# CANBed2040.net
KiCad netlist of a schematic drawn in EAGLE
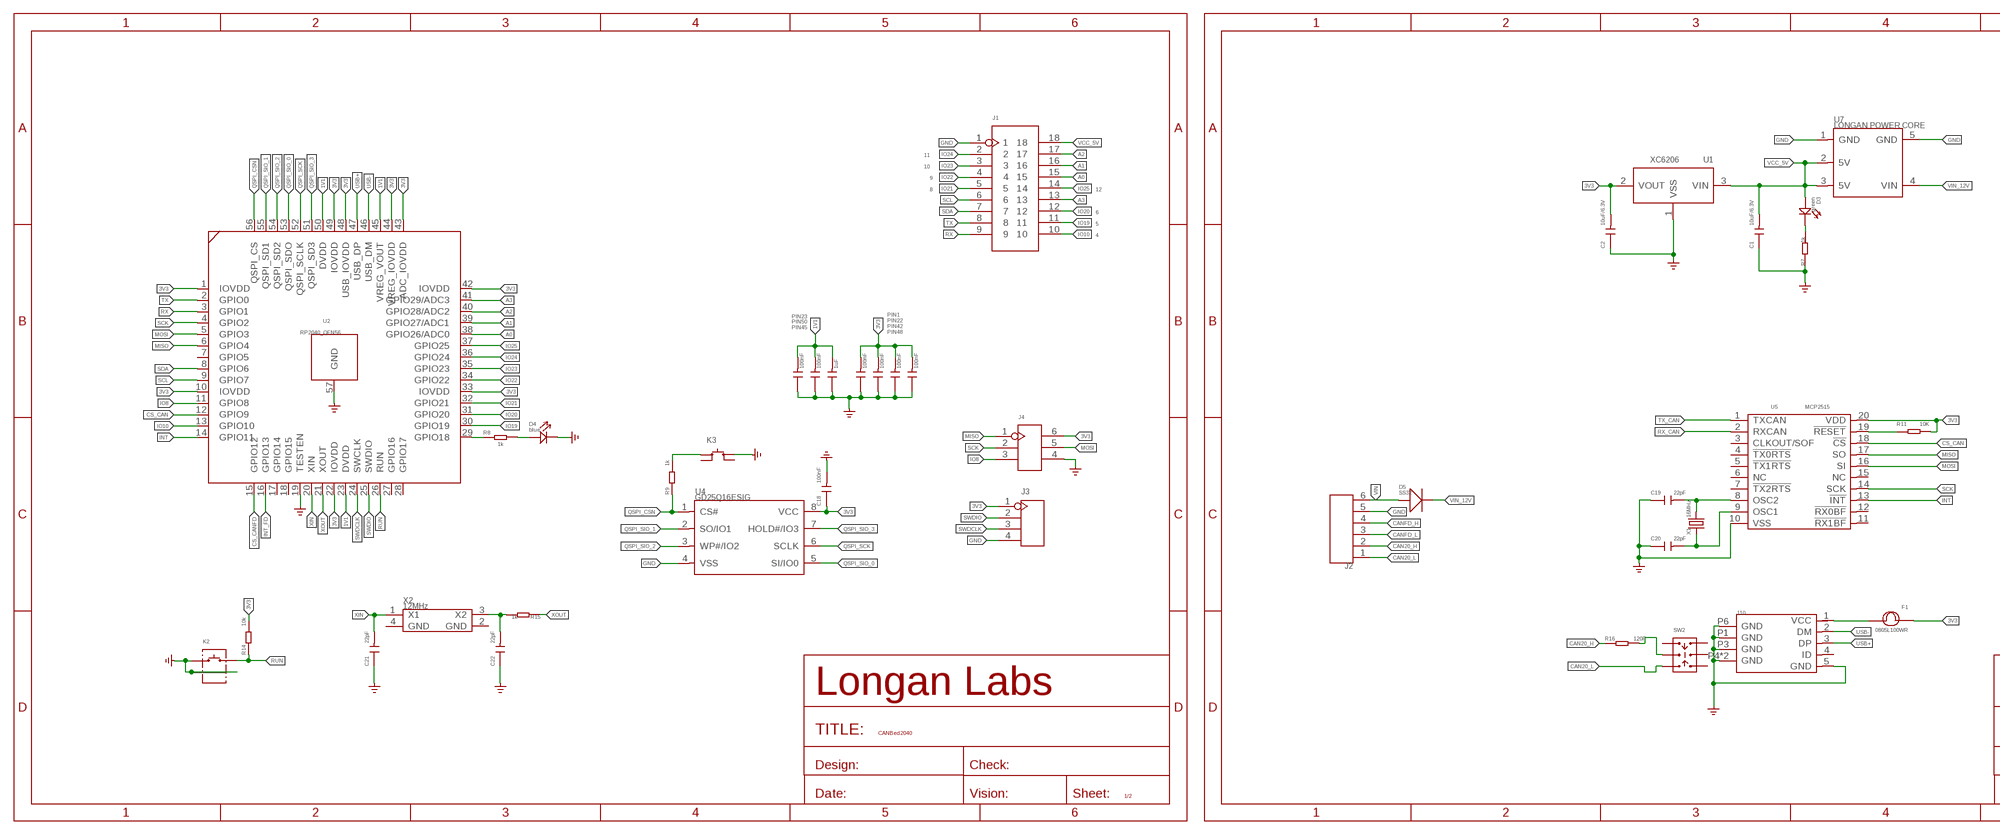
[diagram p0: schematic, sheet 1, part 1 of 2]
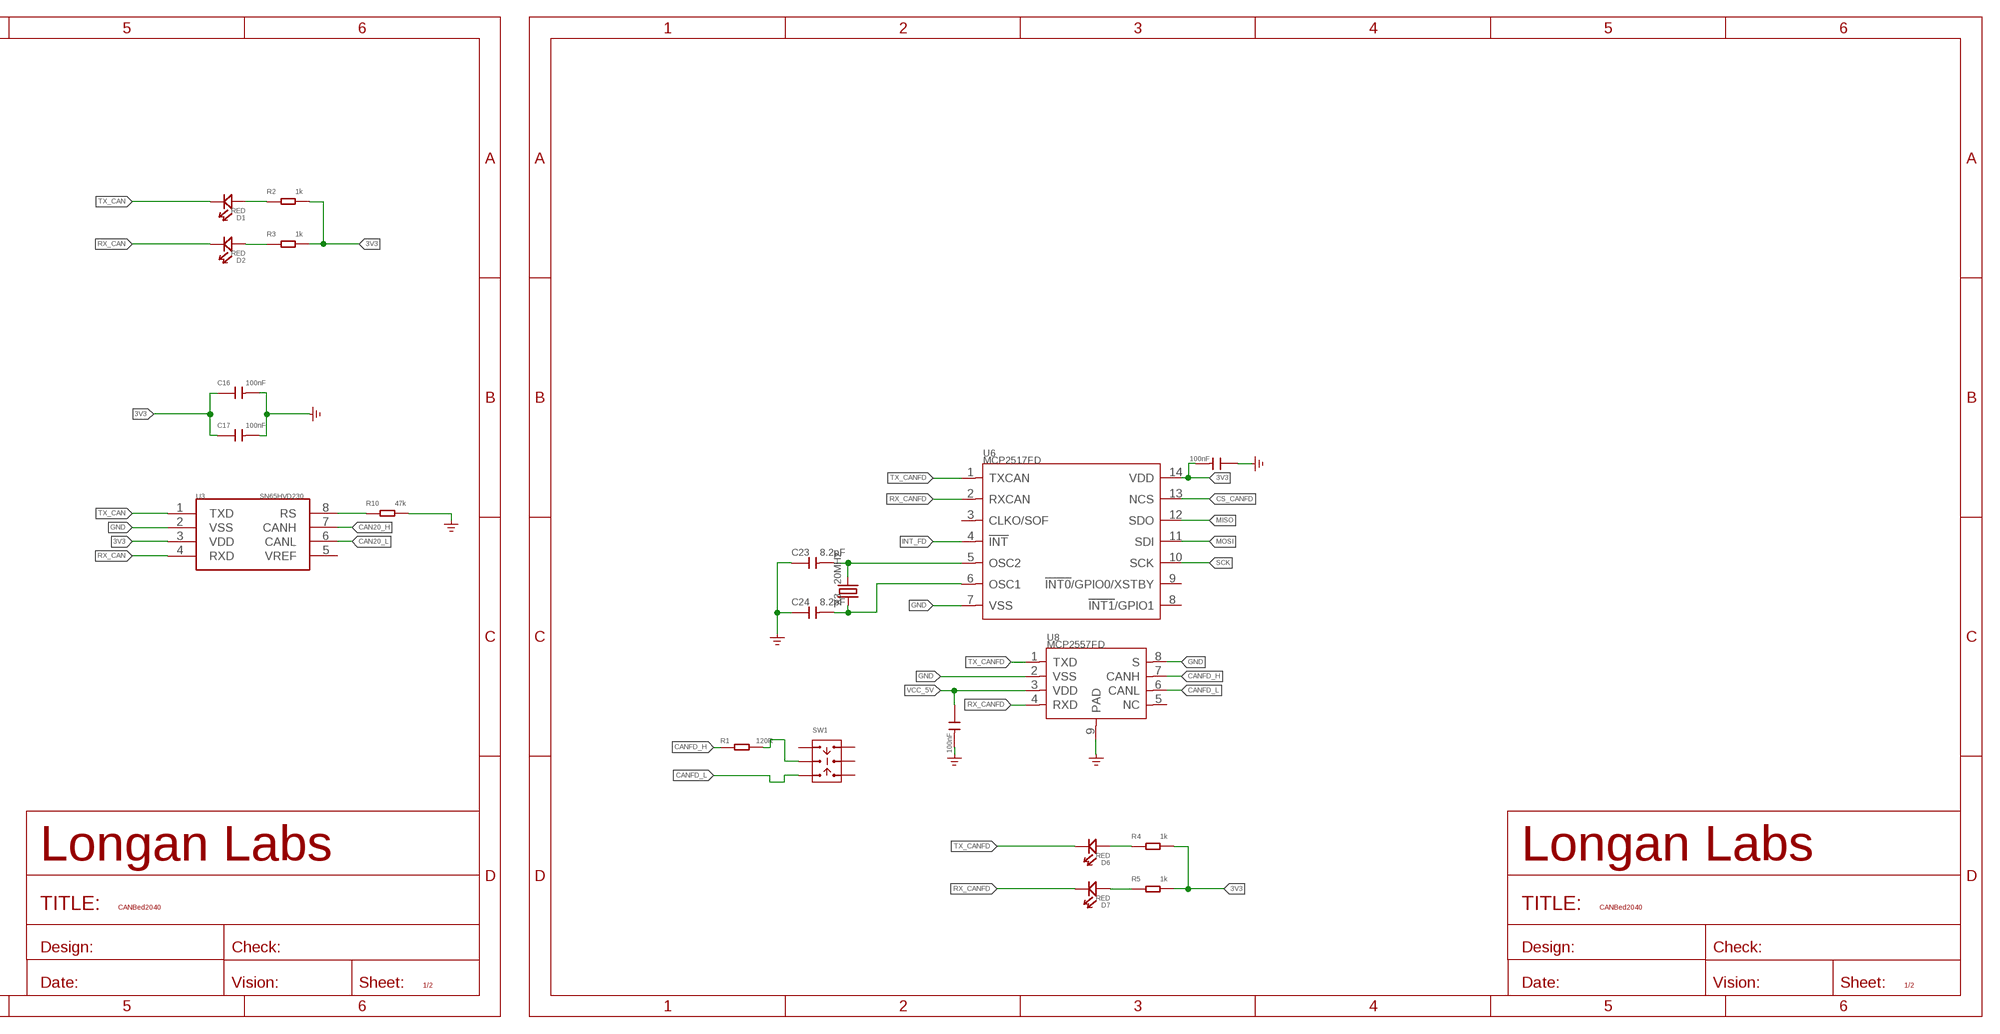
[diagram p1: schematic, sheet 1, part 2 of 2]

(export (version "E")
  (design (tool "Eeschema 10.0.6"))
  (components
    (comp (ref "C1")
      (value "10uF/6.3V")
      (footprint "eagle-import:C0603")
      (libsource (lib "eagle-import") (part "CAP-0603"))
    )
    (comp (ref "C2")
      (value "10uF/6.3V")
      (footprint "eagle-import:C0603")
      (libsource (lib "eagle-import") (part "CAP-0603"))
    )
    (comp (ref "C9")
      (value "100nF")
      (footprint "eagle-import:C0603")
      (libsource (lib "eagle-import") (part "CAP-0603"))
    )
    (comp (ref "C10")
      (value "100nF")
      (footprint "eagle-import:C0603")
      (libsource (lib "eagle-import") (part "CAP-0603"))
    )
    (comp (ref "C11")
      (value "1uF")
      (footprint "eagle-import:C0603")
      (libsource (lib "eagle-import") (part "CAP-0603"))
    )
    (comp (ref "C12")
      (value "100nF")
      (footprint "eagle-import:C0603")
      (libsource (lib "eagle-import") (part "CAP-0603"))
    )
    (comp (ref "C13")
      (value "100nF")
      (footprint "eagle-import:C0603")
      (libsource (lib "eagle-import") (part "CAP-0603"))
    )
    (comp (ref "C14")
      (value "100nF")
      (footprint "eagle-import:C0603")
      (libsource (lib "eagle-import") (part "CAP-0603"))
    )
    (comp (ref "C15")
      (value "100nF")
      (footprint "eagle-import:C0603")
      (libsource (lib "eagle-import") (part "CAP-0603"))
    )
    (comp (ref "C16")
      (value "100nF")
      (footprint "eagle-import:C0603")
      (libsource (lib "eagle-import") (part "CAP-0603"))
    )
    (comp (ref "C17")
      (value "100nF")
      (footprint "eagle-import:C0603")
      (libsource (lib "eagle-import") (part "CAP-0603"))
    )
    (comp (ref "C18")
      (value "100nF")
      (footprint "eagle-import:C0603")
      (libsource (lib "eagle-import") (part "CAP-0603"))
    )
    (comp (ref "C19")
      (value "22pF")
      (footprint "eagle-import:C0603")
      (libsource (lib "eagle-import") (part "CAP-0603"))
    )
    (comp (ref "C20")
      (value "22pF")
      (footprint "eagle-import:C0603")
      (libsource (lib "eagle-import") (part "CAP-0603"))
    )
    (comp (ref "C21")
      (value "22pF")
      (footprint "eagle-import:C0603")
      (libsource (lib "eagle-import") (part "CAP-0603"))
    )
    (comp (ref "C22")
      (value "22pF")
      (footprint "eagle-import:C0603")
      (libsource (lib "eagle-import") (part "CAP-0603"))
    )
    (comp (ref "C23")
      (value "8.2pF")
      (footprint "eagle-import:C0603")
      (libsource (lib "eagle-import") (part "CAP-0603"))
    )
    (comp (ref "C24")
      (value "8.2pF")
      (footprint "eagle-import:C0603")
      (libsource (lib "eagle-import") (part "CAP-0603"))
    )
    (comp (ref "C25")
      (value "100nF")
      (footprint "eagle-import:C0603")
      (libsource (lib "eagle-import") (part "CAP-0603"))
    )
    (comp (ref "C26")
      (value "100nF")
      (footprint "eagle-import:C0603")
      (libsource (lib "eagle-import") (part "CAP-0603"))
    )
    (comp (ref "D1")
      (value "RED")
      (footprint "eagle-import:LED-0603")
      (libsource (lib "eagle-import") (part "LED'0603'"))
    )
    (comp (ref "D2")
      (value "RED")
      (footprint "eagle-import:LED-0603")
      (libsource (lib "eagle-import") (part "LED'0603'"))
    )
    (comp (ref "D3")
      (value "green")
      (footprint "eagle-import:LED-0603")
      (libsource (lib "eagle-import") (part "LED'0603'"))
    )
    (comp (ref "D4")
      (value "blue")
      (footprint "eagle-import:LED-0603")
      (libsource (lib "eagle-import") (part "LED'0603'"))
    )
    (comp (ref "D5")
      (value "SS32")
      (footprint "eagle-import:DO-214AC")
      (libsource (lib "eagle-import") (part "DIODE'SMA'"))
    )
    (comp (ref "D6")
      (value "RED")
      (footprint "eagle-import:LED-0603")
      (libsource (lib "eagle-import") (part "LED'0603'"))
    )
    (comp (ref "D7")
      (value "RED")
      (footprint "eagle-import:LED-0603")
      (libsource (lib "eagle-import") (part "LED'0603'"))
    )
    (comp (ref "F1")
      (value "0805L100WR")
      (footprint "eagle-import:F0805")
      (libsource (lib "eagle-import") (part "FUSE0805"))
    )
    (comp (ref "J1")
      (value "HEADER-2X9P-2.54")
      (footprint "eagle-import:H2X9-2.54")
      (libsource (lib "eagle-import") (part "HEADER-2X9P-2.54"))
    )
    (comp (ref "J2")
      (value "SCREW-TERMINAL-6P-3.5")
      (footprint "eagle-import:H6-3.5-21.7X7.0MM")
      (libsource (lib "eagle-import") (part "SCREW-TERMINAL-6P-3.5"))
    )
    (comp (ref "J3")
      (value "HEADER-4P-SMD")
      (footprint "eagle-import:H4-SMD-2.54")
      (libsource (lib "eagle-import") (part "HEADER-4P-SMD"))
    )
    (comp (ref "J4")
      (value "HEADER-2X3P-2.54")
      (footprint "eagle-import:H2X3-2.54")
      (libsource (lib "eagle-import") (part "HEADER-2X3P-2.54"))
    )
    (comp (ref "J10")
      (value "MICRO-USB5+4P-320010050")
      (footprint "eagle-import:MICRO-USB5+5P-SMD-0.65-7.2X5.06MM")
      (libsource (lib "eagle-import") (part "MICRO-USB5+4P-320010050"))
    )
    (comp (ref "K2")
      (value "BUTTON-2+2P")
      (footprint "eagle-import:SW2+2P-7.7X2.75X3.95MM")
      (libsource (lib "eagle-import") (part "BUTTON-2+2P"))
    )
    (comp (ref "K3")
      (value "BUTTON-4P-4.5X4.5X3.3MM")
      (footprint "eagle-import:SW4-4.5X4.5X3.3MM")
      (libsource (lib "eagle-import") (part "BUTTON-4P-4.5X4.5X3.3MM"))
    )
    (comp (ref "R1")
      (value "120R")
      (footprint "eagle-import:R0603")
      (libsource (lib "eagle-import") (part "RES-0603"))
    )
    (comp (ref "R2")
      (value "1k")
      (footprint "eagle-import:R0603")
      (libsource (lib "eagle-import") (part "RES-0603"))
    )
    (comp (ref "R3")
      (value "1k")
      (footprint "eagle-import:R0603")
      (libsource (lib "eagle-import") (part "RES-0603"))
    )
    (comp (ref "R4")
      (value "1k")
      (footprint "eagle-import:R0603")
      (libsource (lib "eagle-import") (part "RES-0603"))
    )
    (comp (ref "R5")
      (value "1k")
      (footprint "eagle-import:R0603")
      (libsource (lib "eagle-import") (part "RES-0603"))
    )
    (comp (ref "R7")
      (value "1k")
      (footprint "eagle-import:R0603")
      (libsource (lib "eagle-import") (part "RES-0603"))
    )
    (comp (ref "R8")
      (value "1k")
      (footprint "eagle-import:R0603")
      (libsource (lib "eagle-import") (part "RES-0603"))
    )
    (comp (ref "R9")
      (value "1k")
      (footprint "eagle-import:R0603")
      (libsource (lib "eagle-import") (part "RES-0603"))
    )
    (comp (ref "R10")
      (value "47k")
      (footprint "eagle-import:R0603")
      (libsource (lib "eagle-import") (part "RES-0603"))
    )
    (comp (ref "R11")
      (value "10K")
      (footprint "eagle-import:R0603")
      (libsource (lib "eagle-import") (part "RES-0603"))
    )
    (comp (ref "R14")
      (value "10k")
      (footprint "eagle-import:R0603")
      (libsource (lib "eagle-import") (part "RES-0603"))
    )
    (comp (ref "R15")
      (value "1k")
      (footprint "eagle-import:R0603")
      (libsource (lib "eagle-import") (part "RES-0603"))
    )
    (comp (ref "R16")
      (value "120R")
      (footprint "eagle-import:R0603")
      (libsource (lib "eagle-import") (part "RES-0603"))
    )
    (comp (ref "SW1")
      (value "SWITCH-2CH-6P-311010004")
      (footprint "eagle-import:SW6-2.54-9.0X3.5X3.2+2.0MM")
      (libsource (lib "eagle-import") (part "SWITCH-2CH-6P-311010004"))
    )
    (comp (ref "SW2")
      (value "SWITCH-2CH-6P-311010004")
      (footprint "eagle-import:SW6-2.54-9.0X3.5X3.2+2.0MM")
      (libsource (lib "eagle-import") (part "SWITCH-2CH-6P-311010004"))
    )
    (comp (ref "U1")
      (value "XC6206")
      (footprint "eagle-import:SOT-23")
      (libsource (lib "eagle-import") (part "PMIC-XC6206PMR"))
    )
    (comp (ref "U2")
      (value "RP2040_QFN56")
      (footprint "eagle-import:RP2040_QFN56")
      (libsource (lib "eagle-import") (part "RP2040_QFN56"))
    )
    (comp (ref "U3")
      (value "SN65HVD230")
      (footprint "eagle-import:SOIC8-6.0")
      (libsource (lib "eagle-import") (part "MCP2551-SOIC8"))
    )
    (comp (ref "U4")
      (value "GD25Q16ESIG")
      (footprint "eagle-import:SOP8-1.27-5.3X5.25X2MM")
      (libsource (lib "eagle-import") (part "FLASH-GD25Q16E"))
    )
    (comp (ref "U5")
      (value "MCP2515")
      (footprint "eagle-import:TSSOP20-0.65-6.5X4.4MM")
      (libsource (lib "eagle-import") (part "MCP2515'ST'"))
    )
    (comp (ref "U6")
      (value "MCP2517FD")
      (footprint "eagle-import:SOIC14-1.27-8.6X3.9MM")
      (libsource (lib "eagle-import") (part "CONTROLLER-MCP2517FD"))
    )
    (comp (ref "U7")
      (value "LONGAN POWER CORE")
      (footprint "eagle-import:MOUDLE5P-2.54-19X12MM")
      (libsource (lib "eagle-import") (part "MOUDLE-POWER_CORE"))
    )
    (comp (ref "U8")
      (value "MCP2557FD")
      (footprint "eagle-import:TDFN8-0.5-2X3X0.75MM")
      (libsource (lib "eagle-import") (part "TRANSCEIVER-MCP2557FD"))
    )
    (comp (ref "X1")
      (value "16MHz")
      (footprint "eagle-import:X4-SMD-3.2X2.5X0.7MM")
      (libsource (lib "eagle-import") (part "CRYSTAL-2P-3225"))
    )
    (comp (ref "X2")
      (value "12MHz")
      (footprint "eagle-import:X4-SMD-3.2X2.5X0.7MM")
      (libsource (lib "eagle-import") (part "CRYSTAL-4P-3225"))
    )
    (comp (ref "X3")
      (value "20MHz")
      (footprint "eagle-import:X4-SMD-3.2X2.5X0.7MM")
      (libsource (lib "eagle-import") (part "CRYSTAL-2P-3225"))
    )
  )
  (nets
    (net (code "1") (name "1V1") (class "Default")
      (node (ref "C10") (pin "2") (pinfunction "2_2") (pintype "passive"))
      (node (ref "C11") (pin "2") (pinfunction "2_2") (pintype "passive"))
      (node (ref "C9") (pin "2") (pinfunction "2_2") (pintype "passive"))
      (node (ref "U2") (pin "23") (pinfunction "DVDD_23") (pintype "bidirectional"))
      (node (ref "U2") (pin "45") (pinfunction "VREG_VOUT_45") (pintype "bidirectional"))
      (node (ref "U2") (pin "50") (pinfunction "DVDD_50") (pintype "bidirectional"))
    )
    (net (code "2") (name "3V3") (class "Default")
      (node (ref "C12") (pin "2") (pinfunction "2_2") (pintype "passive"))
      (node (ref "C13") (pin "2") (pinfunction "2_2") (pintype "passive"))
      (node (ref "C14") (pin "2") (pinfunction "2_2") (pintype "passive"))
      (node (ref "C15") (pin "2") (pinfunction "2_2") (pintype "passive"))
      (node (ref "C16") (pin "1") (pinfunction "1_1") (pintype "passive"))
      (node (ref "C17") (pin "1") (pinfunction "1_1") (pintype "passive"))
      (node (ref "C18") (pin "1") (pinfunction "1_1") (pintype "passive"))
      (node (ref "C2") (pin "2") (pinfunction "2_2") (pintype "passive"))
      (node (ref "C25") (pin "2") (pinfunction "2_2") (pintype "passive"))
      (node (ref "F1") (pin "1") (pinfunction "1_1") (pintype "bidirectional"))
      (node (ref "J3") (pin "1") (pinfunction "P$1_1") (pintype "bidirectional"))
      (node (ref "J4") (pin "6") (pinfunction "6_6") (pintype "bidirectional"))
      (node (ref "R11") (pin "2") (pinfunction "2_2") (pintype "passive"))
      (node (ref "R14") (pin "2") (pinfunction "2_2") (pintype "passive"))
      (node (ref "R2") (pin "2") (pinfunction "2_2") (pintype "passive"))
      (node (ref "R3") (pin "2") (pinfunction "2_2") (pintype "passive"))
      (node (ref "R4") (pin "2") (pinfunction "2_2") (pintype "passive"))
      (node (ref "R5") (pin "2") (pinfunction "2_2") (pintype "passive"))
      (node (ref "U1") (pin "2") (pinfunction "VOUT_2") (pintype "bidirectional"))
      (node (ref "U2") (pin "1") (pinfunction "IOVDD_1") (pintype "bidirectional"))
      (node (ref "U2") (pin "10") (pinfunction "IOVDD_10") (pintype "bidirectional"))
      (node (ref "U2") (pin "22") (pinfunction "IOVDD_22") (pintype "bidirectional"))
      (node (ref "U2") (pin "33") (pinfunction "IOVDD_33") (pintype "bidirectional"))
      (node (ref "U2") (pin "42") (pinfunction "IOVDD_42") (pintype "bidirectional"))
      (node (ref "U2") (pin "43") (pinfunction "ADC_IOVDD_43") (pintype "bidirectional"))
      (node (ref "U2") (pin "44") (pinfunction "VREG_IOVDD_44") (pintype "bidirectional"))
      (node (ref "U2") (pin "48") (pinfunction "USB_IOVDD_48") (pintype "bidirectional"))
      (node (ref "U2") (pin "49") (pinfunction "IOVDD_49") (pintype "bidirectional"))
      (node (ref "U3") (pin "3") (pinfunction "VDD_3") (pintype "bidirectional"))
      (node (ref "U4") (pin "8") (pinfunction "VCC_8") (pintype "bidirectional"))
      (node (ref "U5") (pin "20") (pinfunction "VDD_20") (pintype "bidirectional"))
      (node (ref "U6") (pin "14") (pinfunction "VDD_14") (pintype "bidirectional"))
    )
    (net (code "3") (name "A0") (class "Default")
      (node (ref "J1") (pin "15") (pinfunction "15_15") (pintype "bidirectional"))
      (node (ref "U2") (pin "38") (pinfunction "GPIO26/ADC0_38") (pintype "bidirectional"))
    )
    (net (code "4") (name "A1") (class "Default")
      (node (ref "J1") (pin "16") (pinfunction "16_16") (pintype "bidirectional"))
      (node (ref "U2") (pin "39") (pinfunction "GPIO27/ADC1_39") (pintype "bidirectional"))
    )
    (net (code "5") (name "A2") (class "Default")
      (node (ref "J1") (pin "17") (pinfunction "17_17") (pintype "bidirectional"))
      (node (ref "U2") (pin "40") (pinfunction "GPIO28/ADC2_40") (pintype "bidirectional"))
    )
    (net (code "6") (name "A3") (class "Default")
      (node (ref "J1") (pin "13") (pinfunction "13_13") (pintype "bidirectional"))
      (node (ref "U2") (pin "41") (pinfunction "GPIO29/ADC3_41") (pintype "bidirectional"))
    )
    (net (code "7") (name "CAN20_H") (class "Default")
      (node (ref "J2") (pin "2") (pinfunction "2_2") (pintype "bidirectional"))
      (node (ref "R16") (pin "1") (pinfunction "1_1") (pintype "passive"))
      (node (ref "U3") (pin "7") (pinfunction "CANH_7") (pintype "bidirectional"))
    )
    (net (code "8") (name "CAN20_L") (class "Default")
      (node (ref "J2") (pin "1") (pinfunction "1_1") (pintype "bidirectional"))
      (node (ref "SW2") (pin "CH1B") (pinfunction "CH1B_CH1B") (pintype "bidirectional"))
      (node (ref "U3") (pin "6") (pinfunction "CANL_6") (pintype "bidirectional"))
    )
    (net (code "9") (name "CANFD_H") (class "Default")
      (node (ref "J2") (pin "4") (pinfunction "4_4") (pintype "bidirectional"))
      (node (ref "R1") (pin "1") (pinfunction "1_1") (pintype "passive"))
      (node (ref "U8") (pin "7") (pinfunction "CANH_7") (pintype "bidirectional"))
    )
    (net (code "10") (name "CANFD_L") (class "Default")
      (node (ref "J2") (pin "3") (pinfunction "3_3") (pintype "bidirectional"))
      (node (ref "SW1") (pin "CH1B") (pinfunction "CH1B_CH1B") (pintype "bidirectional"))
      (node (ref "U8") (pin "6") (pinfunction "CANL_6") (pintype "bidirectional"))
    )
    (net (code "11") (name "CS_CAN") (class "Default")
      (node (ref "U2") (pin "12") (pinfunction "GPIO9_12") (pintype "bidirectional"))
      (node (ref "U5") (pin "18") (pinfunction "~{CS}_18") (pintype "bidirectional"))
    )
    (net (code "12") (name "CS_CANFD") (class "Default")
      (node (ref "U2") (pin "15") (pinfunction "GPIO12_15") (pintype "bidirectional"))
      (node (ref "U6") (pin "13") (pinfunction "NCS_13") (pintype "bidirectional"))
    )
    (net (code "13") (name "GND") (class "Default")
      (node (ref "C1") (pin "1") (pinfunction "1_1") (pintype "passive"))
      (node (ref "C10") (pin "1") (pinfunction "1_1") (pintype "passive"))
      (node (ref "C11") (pin "1") (pinfunction "1_1") (pintype "passive"))
      (node (ref "C12") (pin "1") (pinfunction "1_1") (pintype "passive"))
      (node (ref "C13") (pin "1") (pinfunction "1_1") (pintype "passive"))
      (node (ref "C14") (pin "1") (pinfunction "1_1") (pintype "passive"))
      (node (ref "C15") (pin "1") (pinfunction "1_1") (pintype "passive"))
      (node (ref "C16") (pin "2") (pinfunction "2_2") (pintype "passive"))
      (node (ref "C17") (pin "2") (pinfunction "2_2") (pintype "passive"))
      (node (ref "C18") (pin "2") (pinfunction "2_2") (pintype "passive"))
      (node (ref "C19") (pin "1") (pinfunction "1_1") (pintype "passive"))
      (node (ref "C2") (pin "1") (pinfunction "1_1") (pintype "passive"))
      (node (ref "C20") (pin "1") (pinfunction "1_1") (pintype "passive"))
      (node (ref "C21") (pin "1") (pinfunction "1_1") (pintype "passive"))
      (node (ref "C22") (pin "1") (pinfunction "1_1") (pintype "passive"))
      (node (ref "C23") (pin "1") (pinfunction "1_1") (pintype "passive"))
      (node (ref "C24") (pin "1") (pinfunction "1_1") (pintype "passive"))
      (node (ref "C25") (pin "1") (pinfunction "1_1") (pintype "passive"))
      (node (ref "C26") (pin "2") (pinfunction "2_2") (pintype "passive"))
      (node (ref "C9") (pin "1") (pinfunction "1_1") (pintype "passive"))
      (node (ref "D4") (pin "-") (pinfunction "-_-") (pintype "passive"))
      (node (ref "J1") (pin "1") (pinfunction "1_1") (pintype "bidirectional"))
      (node (ref "J10") (pin "5") (pinfunction "GND_5") (pintype "bidirectional"))
      (node (ref "J10") (pin "P1") (pinfunction "GND_P1") (pintype "bidirectional"))
      (node (ref "J10") (pin "P3") (pinfunction "GND_P3") (pintype "bidirectional"))
      (node (ref "J10") (pin "P4") (pinfunction "GND_P4") (pintype "bidirectional"))
      (node (ref "J10") (pin "P5") (pinfunction "GND_P5") (pintype "bidirectional"))
      (node (ref "J10") (pin "P6") (pinfunction "GND_P6") (pintype "bidirectional"))
      (node (ref "J2") (pin "5") (pinfunction "5_5") (pintype "bidirectional"))
      (node (ref "J3") (pin "4") (pinfunction "P$4_4") (pintype "bidirectional"))
      (node (ref "J4") (pin "4") (pinfunction "4_4") (pintype "bidirectional"))
      (node (ref "K2") (pin "1") (pinfunction "1_1") (pintype "bidirectional"))
      (node (ref "K2") (pin "S1") (pinfunction "S1_S1") (pintype "bidirectional"))
      (node (ref "K2") (pin "S2") (pinfunction "S2_S2") (pintype "bidirectional"))
      (node (ref "K3") (pin "3") (pinfunction "B0_3") (pintype "bidirectional"))
      (node (ref "R10") (pin "2") (pinfunction "2_2") (pintype "passive"))
      (node (ref "R7") (pin "1") (pinfunction "1_1") (pintype "passive"))
      (node (ref "U1") (pin "1") (pinfunction "VSS_1") (pintype "bidirectional"))
      (node (ref "U2") (pin "19") (pinfunction "TESTEN_19") (pintype "bidirectional"))
      (node (ref "U2") (pin "57") (pinfunction "GND_57") (pintype "bidirectional"))
      (node (ref "U3") (pin "2") (pinfunction "VSS_2") (pintype "bidirectional"))
      (node (ref "U4") (pin "4") (pinfunction "VSS_4") (pintype "bidirectional"))
      (node (ref "U5") (pin "10") (pinfunction "VSS_10") (pintype "bidirectional"))
      (node (ref "U6") (pin "7") (pinfunction "VSS_7") (pintype "bidirectional"))
      (node (ref "U7") (pin "1") (pinfunction "GND_1") (pintype "bidirectional"))
      (node (ref "U7") (pin "5") (pinfunction "GND_5") (pintype "bidirectional"))
      (node (ref "U8") (pin "2") (pinfunction "VSS_2") (pintype "bidirectional"))
      (node (ref "U8") (pin "8") (pinfunction "S_8") (pintype "bidirectional"))
      (node (ref "U8") (pin "9") (pinfunction "PAD_9") (pintype "bidirectional"))
    )
    (net (code "14") (name "INT") (class "Default")
      (node (ref "U2") (pin "14") (pinfunction "GPIO11_14") (pintype "bidirectional"))
      (node (ref "U5") (pin "13") (pinfunction "~{INT}_13") (pintype "bidirectional"))
    )
    (net (code "15") (name "INT_FD") (class "Default")
      (node (ref "U2") (pin "16") (pinfunction "GPIO13_16") (pintype "bidirectional"))
      (node (ref "U6") (pin "4") (pinfunction "~{INT}_4") (pintype "bidirectional"))
    )
    (net (code "16") (name "IO8") (class "Default")
      (node (ref "J4") (pin "3") (pinfunction "3_3") (pintype "bidirectional"))
      (node (ref "U2") (pin "11") (pinfunction "GPIO8_11") (pintype "bidirectional"))
    )
    (net (code "17") (name "IO10") (class "Default")
      (node (ref "J1") (pin "10") (pinfunction "10_10") (pintype "bidirectional"))
      (node (ref "U2") (pin "13") (pinfunction "GPIO10_13") (pintype "bidirectional"))
    )
    (net (code "18") (name "IO19") (class "Default")
      (node (ref "J1") (pin "11") (pinfunction "11_11") (pintype "bidirectional"))
      (node (ref "U2") (pin "30") (pinfunction "GPIO19_30") (pintype "bidirectional"))
    )
    (net (code "19") (name "IO20") (class "Default")
      (node (ref "J1") (pin "12") (pinfunction "12_12") (pintype "bidirectional"))
      (node (ref "U2") (pin "31") (pinfunction "GPIO20_31") (pintype "bidirectional"))
    )
    (net (code "20") (name "IO21") (class "Default")
      (node (ref "J1") (pin "5") (pinfunction "5_5") (pintype "bidirectional"))
      (node (ref "U2") (pin "32") (pinfunction "GPIO21_32") (pintype "bidirectional"))
    )
    (net (code "21") (name "IO22") (class "Default")
      (node (ref "J1") (pin "4") (pinfunction "4_4") (pintype "bidirectional"))
      (node (ref "U2") (pin "34") (pinfunction "GPIO22_34") (pintype "bidirectional"))
    )
    (net (code "22") (name "IO23") (class "Default")
      (node (ref "J1") (pin "3") (pinfunction "3_3") (pintype "bidirectional"))
      (node (ref "U2") (pin "35") (pinfunction "GPIO23_35") (pintype "bidirectional"))
    )
    (net (code "23") (name "IO24") (class "Default")
      (node (ref "J1") (pin "2") (pinfunction "2_2") (pintype "bidirectional"))
      (node (ref "U2") (pin "36") (pinfunction "GPIO24_36") (pintype "bidirectional"))
    )
    (net (code "24") (name "IO25") (class "Default")
      (node (ref "J1") (pin "14") (pinfunction "14_14") (pintype "bidirectional"))
      (node (ref "U2") (pin "37") (pinfunction "GPIO25_37") (pintype "bidirectional"))
    )
    (net (code "25") (name "MISO") (class "Default")
      (node (ref "J4") (pin "1") (pinfunction "1_1") (pintype "bidirectional"))
      (node (ref "U2") (pin "6") (pinfunction "GPIO4_6") (pintype "bidirectional"))
      (node (ref "U5") (pin "17") (pinfunction "SO_17") (pintype "bidirectional"))
      (node (ref "U6") (pin "12") (pinfunction "SDO_12") (pintype "bidirectional"))
    )
    (net (code "26") (name "MOSI") (class "Default")
      (node (ref "J4") (pin "5") (pinfunction "5_5") (pintype "bidirectional"))
      (node (ref "U2") (pin "5") (pinfunction "GPIO3_5") (pintype "bidirectional"))
      (node (ref "U5") (pin "16") (pinfunction "SI_16") (pintype "bidirectional"))
      (node (ref "U6") (pin "11") (pinfunction "SDI_11") (pintype "bidirectional"))
    )
    (net (code "27") (name "Net-(D1-Pad+)") (class "Default")
      (node (ref "D1") (pin "+") (pinfunction "+_+") (pintype "passive"))
      (node (ref "R2") (pin "1") (pinfunction "1_1") (pintype "passive"))
    )
    (net (code "28") (name "Net-(D2-Pad+)") (class "Default")
      (node (ref "D2") (pin "+") (pinfunction "+_+") (pintype "passive"))
      (node (ref "R3") (pin "1") (pinfunction "1_1") (pintype "passive"))
    )
    (net (code "29") (name "Net-(D3-Pad-)") (class "Default")
      (node (ref "D3") (pin "-") (pinfunction "-_-") (pintype "passive"))
      (node (ref "R7") (pin "2") (pinfunction "2_2") (pintype "passive"))
    )
    (net (code "30") (name "Net-(D4-Pad+)") (class "Default")
      (node (ref "D4") (pin "+") (pinfunction "+_+") (pintype "passive"))
      (node (ref "R8") (pin "2") (pinfunction "2_2") (pintype "passive"))
    )
    (net (code "31") (name "Net-(D6-Pad+)") (class "Default")
      (node (ref "D6") (pin "+") (pinfunction "+_+") (pintype "passive"))
      (node (ref "R4") (pin "1") (pinfunction "1_1") (pintype "passive"))
    )
    (net (code "32") (name "Net-(D7-Pad+)") (class "Default")
      (node (ref "D7") (pin "+") (pinfunction "+_+") (pintype "passive"))
      (node (ref "R5") (pin "1") (pinfunction "1_1") (pintype "passive"))
    )
    (net (code "33") (name "Net-(J10-VCC)") (class "Default")
      (node (ref "F1") (pin "2") (pinfunction "2_2") (pintype "bidirectional"))
      (node (ref "J10") (pin "1") (pinfunction "VCC_1") (pintype "bidirectional"))
    )
    (net (code "34") (name "Net-(K3-A0)") (class "Default")
      (node (ref "K3") (pin "1") (pinfunction "A0_1") (pintype "bidirectional"))
      (node (ref "R9") (pin "2") (pinfunction "2_2") (pintype "passive"))
    )
    (net (code "35") (name "Net-(R1-Pad2)") (class "Default")
      (node (ref "R1") (pin "2") (pinfunction "2_2") (pintype "passive"))
      (node (ref "SW1") (pin "COM1") (pinfunction "COM1_COM1") (pintype "bidirectional"))
    )
    (net (code "36") (name "Net-(R16-Pad2)") (class "Default")
      (node (ref "R16") (pin "2") (pinfunction "2_2") (pintype "passive"))
      (node (ref "SW2") (pin "COM1") (pinfunction "COM1_COM1") (pintype "bidirectional"))
    )
    (net (code "37") (name "Net-(U2-GPIO18)") (class "Default")
      (node (ref "R8") (pin "1") (pinfunction "1_1") (pintype "passive"))
      (node (ref "U2") (pin "29") (pinfunction "GPIO18_29") (pintype "bidirectional"))
    )
    (net (code "38") (name "Net-(U3-RS)") (class "Default")
      (node (ref "R10") (pin "1") (pinfunction "1_1") (pintype "passive"))
      (node (ref "U3") (pin "8") (pinfunction "RS_8") (pintype "bidirectional"))
    )
    (net (code "39") (name "Net-(U5-OSC1)") (class "Default")
      (node (ref "C20") (pin "2") (pinfunction "2_2") (pintype "passive"))
      (node (ref "U5") (pin "9") (pinfunction "OSC1_9") (pintype "bidirectional"))
      (node (ref "X1") (pin "1") (pinfunction "1_1") (pintype "passive"))
    )
    (net (code "40") (name "Net-(U5-OSC2)") (class "Default")
      (node (ref "C19") (pin "2") (pinfunction "2_2") (pintype "passive"))
      (node (ref "U5") (pin "8") (pinfunction "OSC2_8") (pintype "bidirectional"))
      (node (ref "X1") (pin "3") (pinfunction "2_3") (pintype "passive"))
    )
    (net (code "41") (name "Net-(U5-~{RESET})") (class "Default")
      (node (ref "R11") (pin "1") (pinfunction "1_1") (pintype "passive"))
      (node (ref "U5") (pin "19") (pinfunction "~{RESET}_19") (pintype "bidirectional"))
    )
    (net (code "42") (name "Net-(U6-OSC1)") (class "Default")
      (node (ref "C24") (pin "2") (pinfunction "2_2") (pintype "passive"))
      (node (ref "U6") (pin "6") (pinfunction "OSC1_6") (pintype "bidirectional"))
      (node (ref "X3") (pin "1") (pinfunction "1_1") (pintype "passive"))
    )
    (net (code "43") (name "Net-(U6-OSC2)") (class "Default")
      (node (ref "C23") (pin "2") (pinfunction "2_2") (pintype "passive"))
      (node (ref "U6") (pin "5") (pinfunction "OSC2_5") (pintype "bidirectional"))
      (node (ref "X3") (pin "3") (pinfunction "2_3") (pintype "passive"))
    )
    (net (code "44") (name "Net-(X2-X2)") (class "Default")
      (node (ref "C22") (pin "2") (pinfunction "2_2") (pintype "passive"))
      (node (ref "R15") (pin "2") (pinfunction "2_2") (pintype "passive"))
      (node (ref "X2") (pin "3") (pinfunction "X2_3") (pintype "bidirectional"))
    )
    (net (code "45") (name "QSPI_CSN") (class "Default")
      (node (ref "R9") (pin "1") (pinfunction "1_1") (pintype "passive"))
      (node (ref "U2") (pin "56") (pinfunction "QSPI_CS_56") (pintype "bidirectional"))
      (node (ref "U4") (pin "1") (pinfunction "CS#_1") (pintype "bidirectional"))
    )
    (net (code "46") (name "QSPI_SCK") (class "Default")
      (node (ref "U2") (pin "52") (pinfunction "QSPI_SCLK_52") (pintype "bidirectional"))
      (node (ref "U4") (pin "6") (pinfunction "SCLK_6") (pintype "bidirectional"))
    )
    (net (code "47") (name "QSPI_SIO_0") (class "Default")
      (node (ref "U2") (pin "53") (pinfunction "QSPI_SDO_53") (pintype "bidirectional"))
      (node (ref "U4") (pin "5") (pinfunction "SI/IO0_5") (pintype "bidirectional"))
    )
    (net (code "48") (name "QSPI_SIO_1") (class "Default")
      (node (ref "U2") (pin "55") (pinfunction "QSPI_SD1_55") (pintype "bidirectional"))
      (node (ref "U4") (pin "2") (pinfunction "SO/IO1_2") (pintype "bidirectional"))
    )
    (net (code "49") (name "QSPI_SIO_2") (class "Default")
      (node (ref "U2") (pin "54") (pinfunction "QSPI_SD2_54") (pintype "bidirectional"))
      (node (ref "U4") (pin "3") (pinfunction "WP#/IO2_3") (pintype "bidirectional"))
    )
    (net (code "50") (name "QSPI_SIO_3") (class "Default")
      (node (ref "U2") (pin "51") (pinfunction "QSPI_SD3_51") (pintype "bidirectional"))
      (node (ref "U4") (pin "7") (pinfunction "HOLD#/IO3_7") (pintype "bidirectional"))
    )
    (net (code "51") (name "RUN") (class "Default")
      (node (ref "K2") (pin "2") (pinfunction "2_2") (pintype "bidirectional"))
      (node (ref "R14") (pin "1") (pinfunction "1_1") (pintype "passive"))
      (node (ref "U2") (pin "26") (pinfunction "RUN_26") (pintype "bidirectional"))
    )
    (net (code "52") (name "RX") (class "Default")
      (node (ref "J1") (pin "9") (pinfunction "9_9") (pintype "bidirectional"))
      (node (ref "U2") (pin "3") (pinfunction "GPIO1_3") (pintype "bidirectional"))
    )
    (net (code "53") (name "RX_CAN") (class "Default")
      (node (ref "D2") (pin "-") (pinfunction "-_-") (pintype "passive"))
      (node (ref "U3") (pin "4") (pinfunction "RXD_4") (pintype "bidirectional"))
      (node (ref "U5") (pin "2") (pinfunction "RXCAN_2") (pintype "bidirectional"))
    )
    (net (code "54") (name "RX_CANFD") (class "Default")
      (node (ref "D7") (pin "-") (pinfunction "-_-") (pintype "passive"))
      (node (ref "U6") (pin "2") (pinfunction "RXCAN_2") (pintype "bidirectional"))
      (node (ref "U8") (pin "4") (pinfunction "RXD_4") (pintype "bidirectional"))
    )
    (net (code "55") (name "SCK") (class "Default")
      (node (ref "J4") (pin "2") (pinfunction "2_2") (pintype "bidirectional"))
      (node (ref "U2") (pin "4") (pinfunction "GPIO2_4") (pintype "bidirectional"))
      (node (ref "U5") (pin "14") (pinfunction "SCK_14") (pintype "bidirectional"))
      (node (ref "U6") (pin "10") (pinfunction "SCK_10") (pintype "bidirectional"))
    )
    (net (code "56") (name "SCL") (class "Default")
      (node (ref "J1") (pin "6") (pinfunction "6_6") (pintype "bidirectional"))
      (node (ref "U2") (pin "9") (pinfunction "GPIO7_9") (pintype "bidirectional"))
    )
    (net (code "57") (name "SDA") (class "Default")
      (node (ref "J1") (pin "7") (pinfunction "7_7") (pintype "bidirectional"))
      (node (ref "U2") (pin "8") (pinfunction "GPIO6_8") (pintype "bidirectional"))
    )
    (net (code "58") (name "SWDCLK") (class "Default")
      (node (ref "J3") (pin "3") (pinfunction "P$3_3") (pintype "bidirectional"))
      (node (ref "U2") (pin "24") (pinfunction "SWCLK_24") (pintype "bidirectional"))
    )
    (net (code "59") (name "SWDIO") (class "Default")
      (node (ref "J3") (pin "2") (pinfunction "P$2_2") (pintype "bidirectional"))
      (node (ref "U2") (pin "25") (pinfunction "SWDIO_25") (pintype "bidirectional"))
    )
    (net (code "60") (name "TX") (class "Default")
      (node (ref "J1") (pin "8") (pinfunction "8_8") (pintype "bidirectional"))
      (node (ref "U2") (pin "2") (pinfunction "GPIO0_2") (pintype "bidirectional"))
    )
    (net (code "61") (name "TX_CAN") (class "Default")
      (node (ref "D1") (pin "-") (pinfunction "-_-") (pintype "passive"))
      (node (ref "U3") (pin "1") (pinfunction "TXD_1") (pintype "bidirectional"))
      (node (ref "U5") (pin "1") (pinfunction "TXCAN_1") (pintype "bidirectional"))
    )
    (net (code "62") (name "TX_CANFD") (class "Default")
      (node (ref "D6") (pin "-") (pinfunction "-_-") (pintype "passive"))
      (node (ref "U6") (pin "1") (pinfunction "TXCAN_1") (pintype "bidirectional"))
      (node (ref "U8") (pin "1") (pinfunction "TXD_1") (pintype "bidirectional"))
    )
    (net (code "63") (name "USB+") (class "Default")
      (node (ref "J10") (pin "3") (pinfunction "DP_3") (pintype "bidirectional"))
      (node (ref "U2") (pin "47") (pinfunction "USB_DP_47") (pintype "bidirectional"))
    )
    (net (code "64") (name "USB-") (class "Default")
      (node (ref "J10") (pin "2") (pinfunction "DM_2") (pintype "bidirectional"))
      (node (ref "U2") (pin "46") (pinfunction "USB_DM_46") (pintype "bidirectional"))
    )
    (net (code "65") (name "VCC_5V") (class "Default")
      (node (ref "C1") (pin "2") (pinfunction "2_2") (pintype "passive"))
      (node (ref "C26") (pin "1") (pinfunction "1_1") (pintype "passive"))
      (node (ref "D3") (pin "+") (pinfunction "+_+") (pintype "passive"))
      (node (ref "J1") (pin "18") (pinfunction "18_18") (pintype "bidirectional"))
      (node (ref "U1") (pin "3") (pinfunction "VIN_3") (pintype "bidirectional"))
      (node (ref "U7") (pin "2") (pinfunction "5V_2") (pintype "bidirectional"))
      (node (ref "U7") (pin "3") (pinfunction "5V_3") (pintype "bidirectional"))
      (node (ref "U8") (pin "3") (pinfunction "VDD_3") (pintype "bidirectional"))
    )
    (net (code "66") (name "VIN") (class "Default")
      (node (ref "D5") (pin "1") (pinfunction "+_1") (pintype "passive"))
      (node (ref "J2") (pin "6") (pinfunction "6_6") (pintype "bidirectional"))
    )
    (net (code "67") (name "VIN_12V") (class "Default")
      (node (ref "D5") (pin "2") (pinfunction "-_2") (pintype "passive"))
      (node (ref "U7") (pin "4") (pinfunction "VIN_4") (pintype "bidirectional"))
    )
    (net (code "68") (name "XIN") (class "Default")
      (node (ref "C21") (pin "2") (pinfunction "2_2") (pintype "passive"))
      (node (ref "U2") (pin "20") (pinfunction "XIN_20") (pintype "bidirectional"))
      (node (ref "X2") (pin "1") (pinfunction "X1_1") (pintype "bidirectional"))
    )
    (net (code "69") (name "XOUT") (class "Default")
      (node (ref "R15") (pin "1") (pinfunction "1_1") (pintype "passive"))
      (node (ref "U2") (pin "21") (pinfunction "XOUT_21") (pintype "bidirectional"))
    )
    (net (code "70") (name "unconnected-(J10-ID-Pad4)") (class "Default")
      (node (ref "J10") (pin "4") (pinfunction "ID_4") (pintype "bidirectional"))
    )
    (net (code "71") (name "unconnected-(K3-A1-Pad2)") (class "Default")
      (node (ref "K3") (pin "2") (pinfunction "A1_2") (pintype "bidirectional"))
    )
    (net (code "72") (name "unconnected-(K3-B1-Pad4)") (class "Default")
      (node (ref "K3") (pin "4") (pinfunction "B1_4") (pintype "bidirectional"))
    )
    (net (code "73") (name "unconnected-(SW1-PadCH1A)") (class "Default")
      (node (ref "SW1") (pin "CH1A") (pinfunction "CH1A_CH1A") (pintype "bidirectional"))
    )
    (net (code "74") (name "unconnected-(SW1-PadCH2A)") (class "Default")
      (node (ref "SW1") (pin "CH2A") (pinfunction "CH2A_CH2A") (pintype "bidirectional"))
    )
    (net (code "75") (name "unconnected-(SW1-PadCH2B)") (class "Default")
      (node (ref "SW1") (pin "CH2B") (pinfunction "CH2B_CH2B") (pintype "bidirectional"))
    )
    (net (code "76") (name "unconnected-(SW1-PadCOM2)") (class "Default")
      (node (ref "SW1") (pin "COM2") (pinfunction "COM2_COM2") (pintype "bidirectional"))
    )
    (net (code "77") (name "unconnected-(SW2-PadCH1A)") (class "Default")
      (node (ref "SW2") (pin "CH1A") (pinfunction "CH1A_CH1A") (pintype "bidirectional"))
    )
    (net (code "78") (name "unconnected-(SW2-PadCH2A)") (class "Default")
      (node (ref "SW2") (pin "CH2A") (pinfunction "CH2A_CH2A") (pintype "bidirectional"))
    )
    (net (code "79") (name "unconnected-(SW2-PadCH2B)") (class "Default")
      (node (ref "SW2") (pin "CH2B") (pinfunction "CH2B_CH2B") (pintype "bidirectional"))
    )
    (net (code "80") (name "unconnected-(SW2-PadCOM2)") (class "Default")
      (node (ref "SW2") (pin "COM2") (pinfunction "COM2_COM2") (pintype "bidirectional"))
    )
    (net (code "81") (name "unconnected-(U2-GPIO5-Pad7)") (class "Default")
      (node (ref "U2") (pin "7") (pinfunction "GPIO5_7") (pintype "bidirectional"))
    )
    (net (code "82") (name "unconnected-(U2-GPIO14-Pad17)") (class "Default")
      (node (ref "U2") (pin "17") (pinfunction "GPIO14_17") (pintype "bidirectional"))
    )
    (net (code "83") (name "unconnected-(U2-GPIO15-Pad18)") (class "Default")
      (node (ref "U2") (pin "18") (pinfunction "GPIO15_18") (pintype "bidirectional"))
    )
    (net (code "84") (name "unconnected-(U2-GPIO16-Pad27)") (class "Default")
      (node (ref "U2") (pin "27") (pinfunction "GPIO16_27") (pintype "bidirectional"))
    )
    (net (code "85") (name "unconnected-(U2-GPIO17-Pad28)") (class "Default")
      (node (ref "U2") (pin "28") (pinfunction "GPIO17_28") (pintype "bidirectional"))
    )
    (net (code "86") (name "unconnected-(U3-VREF-Pad5)") (class "Default")
      (node (ref "U3") (pin "5") (pinfunction "VREF_5") (pintype "bidirectional"))
    )
    (net (code "87") (name "unconnected-(U5-CLKOUT{slash}SOF-Pad3)") (class "Default")
      (node (ref "U5") (pin "3") (pinfunction "CLKOUT/SOF_3") (pintype "bidirectional"))
    )
    (net (code "88") (name "unconnected-(U5-NC-Pad6)") (class "Default")
      (node (ref "U5") (pin "6") (pinfunction "NC_6") (pintype "bidirectional"))
    )
    (net (code "89") (name "unconnected-(U5-NC-Pad15)") (class "Default")
      (node (ref "U5") (pin "15") (pinfunction "NC_15") (pintype "bidirectional"))
    )
    (net (code "90") (name "unconnected-(U5-~{RX0BF}-Pad12)") (class "Default")
      (node (ref "U5") (pin "12") (pinfunction "~{RX0BF}_12") (pintype "bidirectional"))
    )
    (net (code "91") (name "unconnected-(U5-~{RX1BF}-Pad11)") (class "Default")
      (node (ref "U5") (pin "11") (pinfunction "~{RX1BF}_11") (pintype "bidirectional"))
    )
    (net (code "92") (name "unconnected-(U5-~{TX0RTS}-Pad4)") (class "Default")
      (node (ref "U5") (pin "4") (pinfunction "~{TX0RTS}_4") (pintype "bidirectional"))
    )
    (net (code "93") (name "unconnected-(U5-~{TX1RTS}-Pad5)") (class "Default")
      (node (ref "U5") (pin "5") (pinfunction "~{TX1RTS}_5") (pintype "bidirectional"))
    )
    (net (code "94") (name "unconnected-(U5-~{TX2RTS}-Pad7)") (class "Default")
      (node (ref "U5") (pin "7") (pinfunction "~{TX2RTS}_7") (pintype "bidirectional"))
    )
    (net (code "95") (name "unconnected-(U6-CLKO{slash}SOF-Pad3)") (class "Default")
      (node (ref "U6") (pin "3") (pinfunction "CLKO/SOF_3") (pintype "bidirectional"))
    )
    (net (code "96") (name "unconnected-(U6-~{INT0}{slash}GPIO0{slash}XSTBY-Pad9)") (class "Default")
      (node (ref "U6") (pin "9") (pinfunction "~{INT0}/GPIO0/XSTBY_9") (pintype "bidirectional"))
    )
    (net (code "97") (name "unconnected-(U6-~{INT1}{slash}GPIO1-Pad8)") (class "Default")
      (node (ref "U6") (pin "8") (pinfunction "~{INT1}/GPIO1_8") (pintype "bidirectional"))
    )
    (net (code "98") (name "unconnected-(U8-NC-Pad5)") (class "Default")
      (node (ref "U8") (pin "5") (pinfunction "NC_5") (pintype "bidirectional"))
    )
    (net (code "99") (name "unconnected-(X2-GND-Pad2)") (class "Default")
      (node (ref "X2") (pin "2") (pinfunction "GND_2") (pintype "bidirectional"))
    )
    (net (code "100") (name "unconnected-(X2-GND-Pad4)") (class "Default")
      (node (ref "X2") (pin "4") (pinfunction "GND_4") (pintype "bidirectional"))
    )
  )
)
